# RS232_SelfPowered_Opto.net
KiCad netlist of a schematic drawn in EAGLE
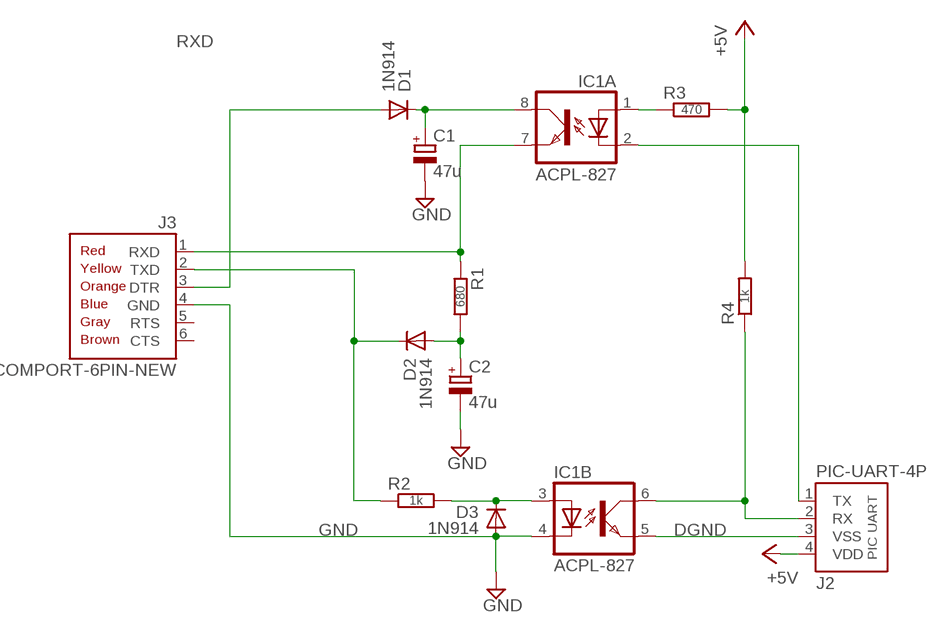
[diagram p0: schematic, sheet 1]

(export (version "E")
  (design (tool "Eeschema 10.0.6"))
  (components
    (comp (ref "C1")
      (value "47u")
      (footprint "eagle-import:E2,5-5")
      (libsource (lib "eagle-import") (part "CPOL-EUE2.5-5"))
    )
    (comp (ref "C2")
      (value "47u")
      (footprint "eagle-import:E2,5-5")
      (libsource (lib "eagle-import") (part "CPOL-EUE2.5-5"))
    )
    (comp (ref "D1")
      (value "1N914")
      (footprint "eagle-import:DO34-7V")
      (libsource (lib "eagle-import") (part "1N414834-7V"))
    )
    (comp (ref "D2")
      (value "1N914")
      (footprint "eagle-import:DO34-7")
      (libsource (lib "eagle-import") (part "1N414834-7"))
    )
    (comp (ref "D3")
      (value "1N914")
      (footprint "eagle-import:DO34-7V")
      (libsource (lib "eagle-import") (part "1N414834-7V"))
    )
    (comp (ref "IC1")
      (value "ACPL-827")
      (footprint "eagle-import:DIL08")
      (libsource (lib "eagle-import") (part "ACPL-827"))
    )
    (comp (ref "J2")
      (value "PIC-UART-4P")
      (footprint "eagle-import:CONN-4P")
      (libsource (lib "eagle-import") (part "PIC-UART-4P"))
    )
    (comp (ref "J3")
      (value "COMPORT-6PIN-NEW")
      (footprint "eagle-import:RS232-6PIN-NEW")
      (libsource (lib "eagle-import") (part "COMPORT-6PIN-NEW"))
    )
    (comp (ref "R1")
      (value "680")
      (footprint "eagle-import:0202_7")
      (libsource (lib "eagle-import") (part "R0202/7"))
    )
    (comp (ref "R2")
      (value "1k")
      (footprint "eagle-import:0202_7")
      (libsource (lib "eagle-import") (part "R0202/7"))
    )
    (comp (ref "R3")
      (value "470")
      (footprint "eagle-import:0202_10-V")
      (libsource (lib "eagle-import") (part "R0202/10-V"))
    )
    (comp (ref "R4")
      (value "1k")
      (footprint "eagle-import:0202_7-V")
      (libsource (lib "eagle-import") (part "R0202/7-V"))
    )
  )
  (nets
    (net (code "1") (name "+5V") (class "Default")
      (node (ref "J2") (pin "4") (pinfunction "VDD_4") (pintype "passive"))
      (node (ref "R3") (pin "2") (pinfunction "2_2") (pintype "passive"))
      (node (ref "R4") (pin "2") (pinfunction "2_2") (pintype "passive"))
    )
    (net (code "2") (name "/DGND") (class "Default")
      (node (ref "IC1") (pin "5") (pinfunction "EMIT_5") (pintype "passive"))
      (node (ref "J2") (pin "3") (pinfunction "VSS_3") (pintype "passive"))
    )
    (net (code "3") (name "/RXD") (class "Default")
      (node (ref "IC1") (pin "7") (pinfunction "EMIT_7") (pintype "passive"))
      (node (ref "J3") (pin "1") (pinfunction "RXD_1") (pintype "passive"))
      (node (ref "R1") (pin "1") (pinfunction "1_1") (pintype "passive"))
    )
    (net (code "4") (name "GND") (class "Default")
      (node (ref "C1") (pin "-") (pinfunction "-_-") (pintype "passive"))
      (node (ref "C2") (pin "-") (pinfunction "-_-") (pintype "passive"))
      (node (ref "D3") (pin "A") (pinfunction "A_A") (pintype "passive"))
      (node (ref "IC1") (pin "4") (pinfunction "C_4") (pintype "passive"))
      (node (ref "J3") (pin "4") (pinfunction "GND_4") (pintype "passive"))
    )
    (net (code "5") (name "Net-(C2-Pad+)") (class "Default")
      (node (ref "C2") (pin "+") (pinfunction "+_+") (pintype "passive"))
      (node (ref "D2") (pin "A") (pinfunction "A_A") (pintype "passive"))
      (node (ref "R1") (pin "2") (pinfunction "2_2") (pintype "passive"))
    )
    (net (code "6") (name "Net-(IC1A-A)") (class "Default")
      (node (ref "IC1") (pin "1") (pinfunction "A_1") (pintype "passive"))
      (node (ref "R3") (pin "1") (pinfunction "1_1") (pintype "passive"))
    )
    (net (code "7") (name "Net-(IC1A-C)") (class "Default")
      (node (ref "IC1") (pin "2") (pinfunction "C_2") (pintype "passive"))
      (node (ref "J2") (pin "1") (pinfunction "TX_1") (pintype "passive"))
    )
    (net (code "8") (name "Net-(IC1A-COL)") (class "Default")
      (node (ref "C1") (pin "+") (pinfunction "+_+") (pintype "passive"))
      (node (ref "D1") (pin "C") (pinfunction "C_C") (pintype "passive"))
      (node (ref "IC1") (pin "8") (pinfunction "COL_8") (pintype "passive"))
    )
    (net (code "9") (name "Net-(IC1B-A)") (class "Default")
      (node (ref "D3") (pin "C") (pinfunction "C_C") (pintype "passive"))
      (node (ref "IC1") (pin "3") (pinfunction "A_3") (pintype "passive"))
      (node (ref "R2") (pin "2") (pinfunction "2_2") (pintype "passive"))
    )
    (net (code "10") (name "Net-(IC1B-COL)") (class "Default")
      (node (ref "IC1") (pin "6") (pinfunction "COL_6") (pintype "passive"))
      (node (ref "J2") (pin "2") (pinfunction "RX_2") (pintype "passive"))
      (node (ref "R4") (pin "1") (pinfunction "1_1") (pintype "passive"))
    )
    (net (code "11") (name "Net-(J3-DTR)") (class "Default")
      (node (ref "D1") (pin "A") (pinfunction "A_A") (pintype "passive"))
      (node (ref "J3") (pin "3") (pinfunction "DTR_3") (pintype "passive"))
    )
    (net (code "12") (name "Net-(J3-TXD)") (class "Default")
      (node (ref "D2") (pin "C") (pinfunction "C_C") (pintype "passive"))
      (node (ref "J3") (pin "2") (pinfunction "TXD_2") (pintype "passive"))
      (node (ref "R2") (pin "1") (pinfunction "1_1") (pintype "passive"))
    )
    (net (code "13") (name "unconnected-(J3-CTS-Pad6)") (class "Default")
      (node (ref "J3") (pin "6") (pinfunction "CTS_6") (pintype "passive"))
    )
    (net (code "14") (name "unconnected-(J3-RTS-Pad5)") (class "Default")
      (node (ref "J3") (pin "5") (pinfunction "RTS_5") (pintype "passive"))
    )
  )
)
